# Encoder_1.net
KiCad netlist of a schematic drawn in Altium Designer
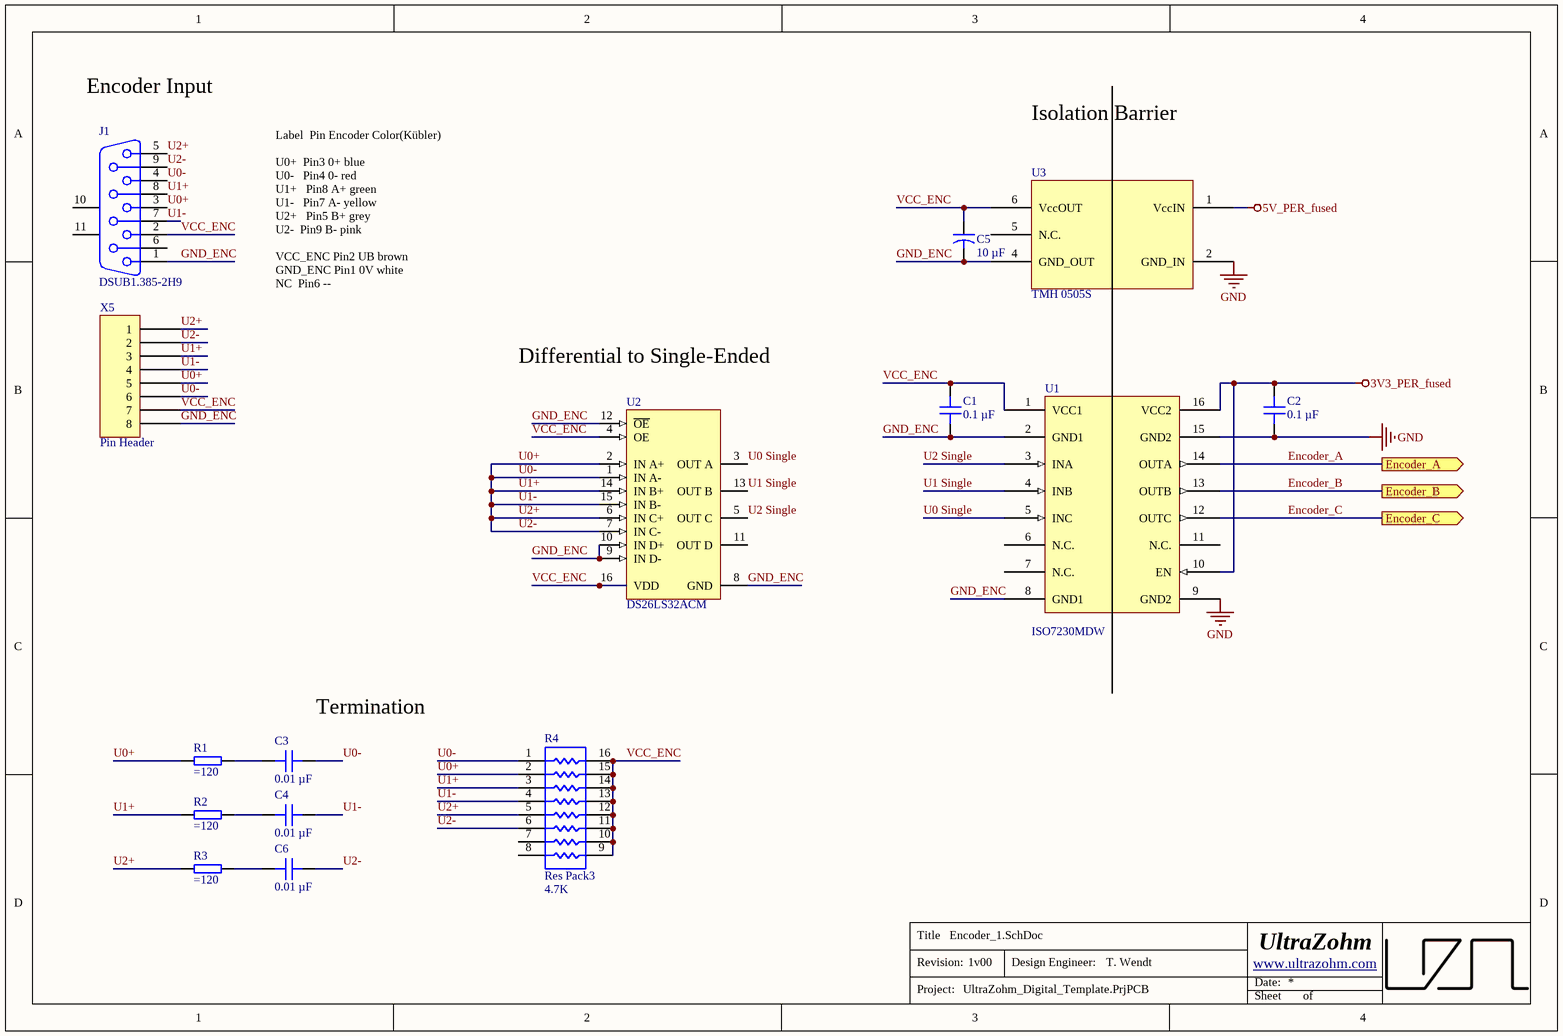
[diagram p0: Encoder_1.SchDoc]

(export (version "E")
  (design (tool "Eeschema 10.0.6"))
  (components
    (comp (ref "C1")
      (value "0.1 µF")
      (footprint "C_0805")
      (description "Capacitor 0805, 50 VDC, 0.1 µF, X7R")
      (fields
        (field (name "MANUFACTURER PART NUMBER") "C0805C104J5RECTU")
        (field (name "MANUFACTURER") "KEMET")
        (field (name "CREATED FROM") "MGremer")
      )
      (libsource (lib "user") (part "Capacitor"))
    )
    (comp (ref "C2")
      (value "0.1 µF")
      (footprint "C_0805")
      (description "Capacitor 0805, 50 VDC, 0.1 µF, X7R")
      (fields
        (field (name "MANUFACTURER PART NUMBER") "C0805C104J5RECTU")
        (field (name "MANUFACTURER") "KEMET")
        (field (name "CREATED FROM") "MGremer")
      )
      (libsource (lib "user") (part "Capacitor"))
    )
    (comp (ref "C3")
      (value "0.01 µF")
      (footprint "C_0805")
      (description "Capacitor 0805, 100 VDC, 0.01 µF, X7R")
      (fields
        (field (name "MANUFACTURER PART NUMBER") "GRM21BR72A103KA01L")
        (field (name "MANUFACTURER") "Murata Electronics")
        (field (name "CREATED FROM") "MGremer")
      )
      (libsource (lib "user") (part "Capacitor"))
    )
    (comp (ref "C4")
      (value "0.01 µF")
      (footprint "C_0805")
      (description "Capacitor 0805, 100 VDC, 0.01 µF, X7R")
      (fields
        (field (name "MANUFACTURER PART NUMBER") "GRM21BR72A103KA01L")
        (field (name "MANUFACTURER") "Murata Electronics")
        (field (name "CREATED FROM") "MGremer")
      )
      (libsource (lib "user") (part "Capacitor"))
    )
    (comp (ref "C5")
      (value "10 µF")
      (footprint "CAPR5-4X5")
      (description "Capacitor; 2 Leads")
      (fields
        (field (name "MANUFACTURER PART NUMBER") "CAPR5-4X5")
        (field (name "PUBLISHER") "Altium Limited")
        (field (name "CREATED FROM") "MHlatky")
      )
      (libsource (lib "user") (part "Cap2"))
    )
    (comp (ref "C6")
      (value "0.01 µF")
      (footprint "C_0805")
      (description "Capacitor 0805, 100 VDC, 0.01 µF, X7R")
      (fields
        (field (name "MANUFACTURER PART NUMBER") "GRM21BR72A103KA01L")
        (field (name "MANUFACTURER") "Murata Electronics")
        (field (name "CREATED FROM") "MGremer")
      )
      (libsource (lib "user") (part "Capacitor"))
    )
    (comp (ref "J1")
      (value "DSUB1.385-2H9")
      (footprint "DSUB1.385-2H9")
      (description "Connector; D Subminiature; 9 Position; Right Angle; Pitch 1.385 mm")
      (fields
        (field (name "MANUFACTURER") "Altium")
        (field (name "PUBLISHER") "Altium Limited")
        (field (name "CREATED FROM") "MHlatky")
      )
      (libsource (lib "user") (part "D Connector 9"))
    )
    (comp (ref "R1")
      (value "~")
      (footprint "RES 0805_2012")
      (description "SMD resistor 1%")
      (fields
        (field (name "MANUFACTURER PART NUMBER") "ERJ-6ENF1182V")
        (field (name "MANUFACTURER") "Panasonic")
        (field (name "CREATED FROM") "MGremer")
      )
      (libsource (lib "user") (part "Resistor"))
    )
    (comp (ref "R2")
      (value "~")
      (footprint "RES 0805_2012")
      (description "SMD resistor 1%")
      (fields
        (field (name "MANUFACTURER PART NUMBER") "ERJ-6ENF1182V")
        (field (name "MANUFACTURER") "Panasonic")
        (field (name "CREATED FROM") "MGremer")
      )
      (libsource (lib "user") (part "Resistor"))
    )
    (comp (ref "R3")
      (value "~")
      (footprint "RES 0805_2012")
      (description "SMD resistor 1%")
      (fields
        (field (name "MANUFACTURER PART NUMBER") "ERJ-6ENF1182V")
        (field (name "MANUFACTURER") "Panasonic")
        (field (name "CREATED FROM") "MGremer")
      )
      (libsource (lib "user") (part "Resistor"))
    )
    (comp (ref "R4")
      (value "Res Pack3")
      (footprint "SO-16_N")
      (description "SOIC, 16-Leads, Body 9.9x3.9mm, Pitch 1.27mm, IPC Medium Density")
      (fields
        (field (name "ALTIUM_VALUE") "4.7K")
        (field (name "PUBLISHER") "Altium Limited")
        (field (name "CREATED FROM") "MHlatky")
      )
      (libsource (lib "user") (part "Res Pack3"))
    )
    (comp (ref "U1")
      (value "ISO7230MDW")
      (footprint "TI ISO7230 SOIC")
      (description "ISO723xx High-Speed, Triple-Channel Digital Isolators")
      (fields (field (name "MANUFACTURER") "Analog Devices") (field (name "CREATED FROM") "MHlatky"))
      (libsource (lib "user") (part "TI ISO7230"))
    )
    (comp (ref "U2")
      (value "DS26LS32ACM")
      (footprint "M16A_M")
      (description "DS26LS32AC/DS26LS32C/DS26LS32M/DS26LS33M Quad Differential Line Receivers")
      (fields
        (field (name "MANUFACTURER") "Texas Instruments")
        (field (name "PUBLISHER") "Altium Limited")
        (field (name "CREATED FROM") "MHlatky")
      )
      (libsource (lib "user") (part "DS26LS32ACM"))
    )
    (comp (ref "U3")
      (value "TMH 0505S")
      (footprint "SIL-6(7)")
      (fields (field (name "MANUFACTURER") "Traco") (field (name "CREATED FROM") "MHlatky"))
      (libsource (lib "user") (part "TRACO TMH 0505S"))
    )
    (comp (ref "X5")
      (value "Pin Header")
      (footprint "HDR1X8")
      (description "8 Pin")
      (fields (field (name "MANUFACTURER PART NUMBER") "HDR1X8") (field (name "CREATED FROM") "MHlatky"))
      (libsource (lib "user") (part "8 Pin"))
    )
  )
  (nets
    (net (code "1") (name "/Encoder_A") (class "Default")
      (node (ref "U1") (pin "14") (pinfunction "OUTA_14") (pintype "output"))
    )
    (net (code "2") (name "/Encoder_B") (class "Default")
      (node (ref "U1") (pin "13") (pinfunction "OUTB_13") (pintype "output"))
    )
    (net (code "3") (name "/Encoder_C") (class "Default")
      (node (ref "U1") (pin "12") (pinfunction "OUTC_12") (pintype "output"))
    )
    (net (code "4") (name "/GND_ENC") (class "Default")
      (node (ref "C1") (pin "1") (pinfunction "1_1") (pintype "passive"))
      (node (ref "C5") (pin "2") (pinfunction "2_2") (pintype "passive"))
      (node (ref "J1") (pin "1") (pinfunction "1_1") (pintype "passive"))
      (node (ref "U1") (pin "2") (pinfunction "GND1_2") (pintype "passive"))
      (node (ref "U1") (pin "8") (pinfunction "GND1_8") (pintype "passive"))
      (node (ref "U2") (pin "10") (pinfunction "IN_D+_10") (pintype "input"))
      (node (ref "U2") (pin "12") (pinfunction "~{OE}_12") (pintype "input"))
      (node (ref "U2") (pin "8") (pinfunction "GND_8") (pintype "power_in"))
      (node (ref "U2") (pin "9") (pinfunction "IN_D-_9") (pintype "input"))
      (node (ref "U3") (pin "4") (pinfunction "GND_OUT_4") (pintype "passive"))
      (node (ref "X5") (pin "8") (pinfunction "8_8") (pintype "passive"))
    )
    (net (code "5") (name "/U0 Single") (class "Default")
      (node (ref "U1") (pin "5") (pinfunction "INC_5") (pintype "input"))
      (node (ref "U2") (pin "3") (pinfunction "OUT_A_3") (pintype "tri_state"))
    )
    (net (code "6") (name "/U0+") (class "Default")
      (node (ref "C3") (pin "2") (pinfunction "2_2") (pintype "passive"))
      (node (ref "C4") (pin "2") (pinfunction "2_2") (pintype "passive"))
      (node (ref "C6") (pin "2") (pinfunction "2_2") (pintype "passive"))
      (node (ref "J1") (pin "3") (pinfunction "3_3") (pintype "passive"))
      (node (ref "J1") (pin "4") (pinfunction "4_4") (pintype "passive"))
      (node (ref "J1") (pin "5") (pinfunction "5_5") (pintype "passive"))
      (node (ref "J1") (pin "7") (pinfunction "7_7") (pintype "passive"))
      (node (ref "J1") (pin "8") (pinfunction "8_8") (pintype "passive"))
      (node (ref "J1") (pin "9") (pinfunction "9_9") (pintype "passive"))
      (node (ref "R1") (pin "1") (pinfunction "1_1") (pintype "passive"))
      (node (ref "R2") (pin "1") (pinfunction "1_1") (pintype "passive"))
      (node (ref "R3") (pin "1") (pinfunction "1_1") (pintype "passive"))
      (node (ref "R4") (pin "1") (pinfunction "1_1") (pintype "passive"))
      (node (ref "R4") (pin "2") (pinfunction "2_2") (pintype "passive"))
      (node (ref "R4") (pin "3") (pinfunction "3_3") (pintype "passive"))
      (node (ref "R4") (pin "4") (pinfunction "4_4") (pintype "passive"))
      (node (ref "R4") (pin "5") (pinfunction "5_5") (pintype "passive"))
      (node (ref "R4") (pin "6") (pinfunction "6_6") (pintype "passive"))
      (node (ref "U2") (pin "1") (pinfunction "IN_A-_1") (pintype "input"))
      (node (ref "U2") (pin "14") (pinfunction "IN_B+_14") (pintype "input"))
      (node (ref "U2") (pin "15") (pinfunction "IN_B-_15") (pintype "input"))
      (node (ref "U2") (pin "2") (pinfunction "IN_A+_2") (pintype "input"))
      (node (ref "U2") (pin "6") (pinfunction "IN_C+_6") (pintype "input"))
      (node (ref "U2") (pin "7") (pinfunction "IN_C-_7") (pintype "input"))
      (node (ref "X5") (pin "1") (pinfunction "1_1") (pintype "passive"))
      (node (ref "X5") (pin "2") (pinfunction "2_2") (pintype "passive"))
      (node (ref "X5") (pin "3") (pinfunction "3_3") (pintype "passive"))
      (node (ref "X5") (pin "4") (pinfunction "4_4") (pintype "passive"))
      (node (ref "X5") (pin "5") (pinfunction "5_5") (pintype "passive"))
      (node (ref "X5") (pin "6") (pinfunction "6_6") (pintype "passive"))
    )
    (net (code "7") (name "/U1 Single") (class "Default")
      (node (ref "U1") (pin "4") (pinfunction "INB_4") (pintype "input"))
      (node (ref "U2") (pin "13") (pinfunction "OUT_B_13") (pintype "tri_state"))
    )
    (net (code "8") (name "/U2 Single") (class "Default")
      (node (ref "U1") (pin "3") (pinfunction "INA_3") (pintype "input"))
      (node (ref "U2") (pin "5") (pinfunction "OUT_C_5") (pintype "tri_state"))
    )
    (net (code "9") (name "/VCC_ENC") (class "Default")
      (node (ref "C1") (pin "2") (pinfunction "2_2") (pintype "passive"))
      (node (ref "C5") (pin "1") (pinfunction "1_1") (pintype "passive"))
      (node (ref "J1") (pin "2") (pinfunction "2_2") (pintype "passive"))
      (node (ref "R4") (pin "10") (pinfunction "10_10") (pintype "passive"))
      (node (ref "R4") (pin "11") (pinfunction "11_11") (pintype "passive"))
      (node (ref "R4") (pin "12") (pinfunction "12_12") (pintype "passive"))
      (node (ref "R4") (pin "13") (pinfunction "13_13") (pintype "passive"))
      (node (ref "R4") (pin "14") (pinfunction "14_14") (pintype "passive"))
      (node (ref "R4") (pin "15") (pinfunction "15_15") (pintype "passive"))
      (node (ref "R4") (pin "16") (pinfunction "16_16") (pintype "passive"))
      (node (ref "R4") (pin "9") (pinfunction "9_9") (pintype "passive"))
      (node (ref "U1") (pin "1") (pinfunction "VCC1_1") (pintype "passive"))
      (node (ref "U2") (pin "16") (pinfunction "VDD_16") (pintype "power_in"))
      (node (ref "U2") (pin "4") (pinfunction "OE_4") (pintype "input"))
      (node (ref "U3") (pin "6") (pinfunction "VccOUT_6") (pintype "passive"))
      (node (ref "X5") (pin "7") (pinfunction "7_7") (pintype "passive"))
    )
    (net (code "10") (name "3V3_PER_fused") (class "Default")
      (node (ref "C2") (pin "2") (pinfunction "2_2") (pintype "passive"))
      (node (ref "U1") (pin "10") (pinfunction "EN_10") (pintype "input"))
      (node (ref "U1") (pin "16") (pinfunction "VCC2_16") (pintype "passive"))
    )
    (net (code "11") (name "5V_PER_fused") (class "Default")
      (node (ref "U3") (pin "1") (pinfunction "VccIN_1") (pintype "passive"))
    )
    (net (code "12") (name "GND") (class "Default")
      (node (ref "C2") (pin "1") (pinfunction "1_1") (pintype "passive"))
      (node (ref "U1") (pin "15") (pinfunction "GND2_15") (pintype "passive"))
      (node (ref "U1") (pin "9") (pinfunction "GND2_9") (pintype "passive"))
      (node (ref "U3") (pin "2") (pinfunction "GND_IN_2") (pintype "passive"))
    )
    (net (code "13") (name "Net-(C3-Pad1)") (class "Default")
      (node (ref "C3") (pin "1") (pinfunction "1_1") (pintype "passive"))
      (node (ref "R1") (pin "2") (pinfunction "2_2") (pintype "passive"))
    )
    (net (code "14") (name "Net-(C4-Pad1)") (class "Default")
      (node (ref "C4") (pin "1") (pinfunction "1_1") (pintype "passive"))
      (node (ref "R2") (pin "2") (pinfunction "2_2") (pintype "passive"))
    )
    (net (code "15") (name "Net-(C6-Pad1)") (class "Default")
      (node (ref "C6") (pin "1") (pinfunction "1_1") (pintype "passive"))
      (node (ref "R3") (pin "2") (pinfunction "2_2") (pintype "passive"))
    )
    (net (code "16") (name "unconnected-(J1-MH1-Pad10)") (class "Default")
      (node (ref "J1") (pin "10") (pinfunction "MH1_10") (pintype "passive"))
    )
    (net (code "17") (name "unconnected-(J1-MH2-Pad11)") (class "Default")
      (node (ref "J1") (pin "11") (pinfunction "MH2_11") (pintype "passive"))
    )
    (net (code "18") (name "unconnected-(J1-Pad6)") (class "Default")
      (node (ref "J1") (pin "6") (pinfunction "6_6") (pintype "passive"))
    )
    (net (code "19") (name "unconnected-(R4-Pad7)") (class "Default")
      (node (ref "R4") (pin "7") (pinfunction "7_7") (pintype "passive"))
    )
    (net (code "20") (name "unconnected-(R4-Pad8)") (class "Default")
      (node (ref "R4") (pin "8") (pinfunction "8_8") (pintype "passive"))
    )
    (net (code "21") (name "unconnected-(U1-N.C.-Pad6)") (class "Default")
      (node (ref "U1") (pin "6") (pinfunction "N.C._6") (pintype "passive"))
    )
    (net (code "22") (name "unconnected-(U1-N.C.-Pad7)") (class "Default")
      (node (ref "U1") (pin "7") (pinfunction "N.C._7") (pintype "passive"))
    )
    (net (code "23") (name "unconnected-(U1-N.C.-Pad11)") (class "Default")
      (node (ref "U1") (pin "11") (pinfunction "N.C._11") (pintype "passive"))
    )
    (net (code "24") (name "unconnected-(U2-OUT_D-Pad11)") (class "Default")
      (node (ref "U2") (pin "11") (pinfunction "OUT_D_11") (pintype "tri_state"))
    )
    (net (code "25") (name "unconnected-(U3-N.C.-Pad5)") (class "Default")
      (node (ref "U3") (pin "5") (pinfunction "N.C._5") (pintype "passive"))
    )
  )
)
